# PocketAnalyser_CPLBridge_R01.net
KiCad netlist of a schematic drawn in Altium Designer
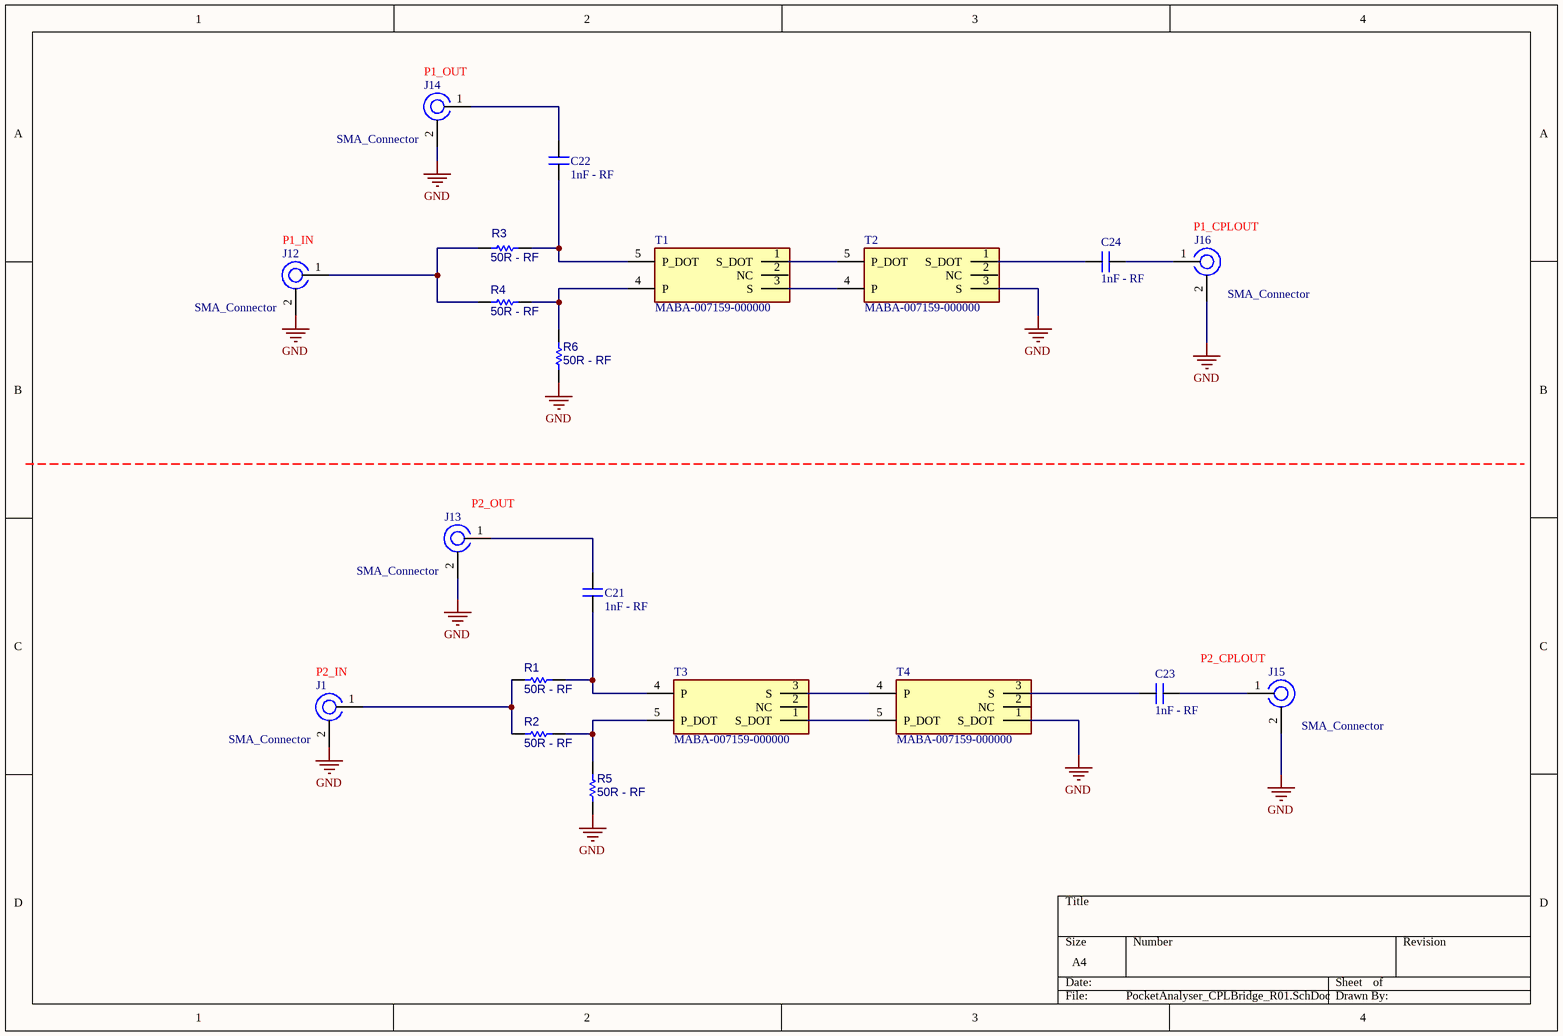
[diagram p0: PocketAnalyser_CPLBridge_R01.SchDoc]

(export (version "E")
  (design (tool "Eeschema 10.0.6"))
  (components
    (comp (ref "C21")
      (value "1nF - RF")
      (footprint "C_0603")
      (libsource (lib "SchLib_PocketAnalyzer") (part "Ceramic Cap"))
    )
    (comp (ref "C22")
      (value "1nF - RF")
      (footprint "C_0603")
      (libsource (lib "SchLib_PocketAnalyzer") (part "Ceramic Cap"))
    )
    (comp (ref "C23")
      (value "1nF - RF")
      (footprint "C_0603")
      (libsource (lib "SchLib_PocketAnalyzer") (part "Ceramic Cap"))
    )
    (comp (ref "C24")
      (value "1nF - RF")
      (footprint "C_0603")
      (libsource (lib "SchLib_PocketAnalyzer") (part "Ceramic Cap"))
    )
    (comp (ref "J1")
      (value "SMA_Connector")
      (footprint "SMA_Connector")
      (description "Connector SMA")
      (libsource (lib "") (part "SMA_Connector_1"))
    )
    (comp (ref "J12")
      (value "SMA_Connector")
      (footprint "SMA_Connector")
      (description "Connector SMA")
      (libsource (lib "") (part "SMA_Connector_1"))
    )
    (comp (ref "J13")
      (value "SMA_Connector")
      (footprint "SMA_Connector")
      (description "Connector SMA")
      (libsource (lib "") (part "SMA_Connector_1"))
    )
    (comp (ref "J14")
      (value "SMA_Connector")
      (footprint "SMA_Connector")
      (description "Connector SMA")
      (libsource (lib "") (part "SMA_Connector_1"))
    )
    (comp (ref "J15")
      (value "SMA_Connector")
      (footprint "SMA_Connector")
      (description "Connector SMA")
      (libsource (lib "SchLib_PocketAnalyzer") (part "SMA_Connector"))
    )
    (comp (ref "J16")
      (value "SMA_Connector")
      (footprint "SMA_Connector")
      (description "Connector SMA")
      (libsource (lib "SchLib_PocketAnalyzer") (part "SMA_Connector"))
    )
    (comp (ref "R1")
      (value "50R - RF")
      (footprint "R_0603")
      (description "Resistor")
      (libsource (lib "SchLib_PocketAnalyzer") (part "Res1"))
    )
    (comp (ref "R2")
      (value "50R - RF")
      (footprint "R_0603")
      (description "Resistor")
      (libsource (lib "SchLib_PocketAnalyzer") (part "Res1"))
    )
    (comp (ref "R3")
      (value "50R - RF")
      (footprint "R_0603")
      (description "Resistor")
      (libsource (lib "SchLib_PocketAnalyzer") (part "Res1"))
    )
    (comp (ref "R4")
      (value "50R - RF")
      (footprint "R_0603")
      (description "Resistor")
      (libsource (lib "SchLib_PocketAnalyzer") (part "Res1"))
    )
    (comp (ref "R5")
      (value "50R - RF")
      (footprint "R_0603")
      (description "Resistor")
      (libsource (lib "SchLib_PocketAnalyzer") (part "Res1"))
    )
    (comp (ref "R6")
      (value "50R - RF")
      (footprint "R_0603")
      (description "Resistor")
      (libsource (lib "SchLib_PocketAnalyzer") (part "Res1"))
    )
    (comp (ref "T1")
      (value "MABA-007159-000000")
      (footprint "MABA-007159-000000_1")
      (description "Transformer")
      (fields (field (name "MOUSER PART NUMBER") "937-MABA007159000000"))
      (libsource (lib "") (part "MABA-007159-000000_1"))
    )
    (comp (ref "T2")
      (value "MABA-007159-000000")
      (footprint "MABA-007159-000000_1")
      (description "Transformer")
      (fields (field (name "MOUSER PART NUMBER") "937-MABA007159000000"))
      (libsource (lib "") (part "MABA-007159-000000_1"))
    )
    (comp (ref "T3")
      (value "MABA-007159-000000")
      (footprint "MABA-007159-000000_1")
      (description "Transformer")
      (fields (field (name "MOUSER PART NUMBER") "937-MABA007159000000"))
      (libsource (lib "SchLib_PocketAnalyzer") (part "MABA-007159-000000"))
    )
    (comp (ref "T4")
      (value "MABA-007159-000000")
      (footprint "MABA-007159-000000_1")
      (description "Transformer")
      (fields (field (name "MOUSER PART NUMBER") "937-MABA007159000000"))
      (libsource (lib "SchLib_PocketAnalyzer") (part "MABA-007159-000000"))
    )
  )
  (nets
    (net (code "1") (name "GND") (class "Default")
      (node (ref "J1") (pin "2") (pinfunction "2_2") (pintype "passive"))
      (node (ref "J12") (pin "2") (pinfunction "2_2") (pintype "passive"))
      (node (ref "J13") (pin "2") (pinfunction "2_2") (pintype "passive"))
      (node (ref "J14") (pin "2") (pinfunction "2_2") (pintype "passive"))
      (node (ref "J15") (pin "2") (pinfunction "2_2") (pintype "passive"))
      (node (ref "J16") (pin "2") (pinfunction "2_2") (pintype "passive"))
      (node (ref "R5") (pin "1") (pinfunction "1_1") (pintype "passive"))
      (node (ref "R6") (pin "1") (pinfunction "1_1") (pintype "passive"))
      (node (ref "T2") (pin "3") (pinfunction "S_3") (pintype "passive"))
      (node (ref "T4") (pin "1") (pinfunction "S_DOT_1") (pintype "passive"))
    )
    (net (code "2") (name "Net-(C21-Pad2)") (class "Default")
      (node (ref "C21") (pin "2") (pintype "passive"))
      (node (ref "J13") (pin "1") (pinfunction "1_1") (pintype "passive"))
    )
    (net (code "3") (name "Net-(C22-Pad2)") (class "Default")
      (node (ref "C22") (pin "2") (pintype "passive"))
      (node (ref "J14") (pin "1") (pinfunction "1_1") (pintype "passive"))
    )
    (net (code "4") (name "Net-(C23-Pad1)") (class "Default")
      (node (ref "C23") (pin "1") (pintype "passive"))
      (node (ref "J15") (pin "1") (pinfunction "1_1") (pintype "passive"))
    )
    (net (code "5") (name "Net-(C24-Pad1)") (class "Default")
      (node (ref "C24") (pin "1") (pintype "passive"))
      (node (ref "J16") (pin "1") (pinfunction "1_1") (pintype "passive"))
    )
    (net (code "6") (name "Net-(J1-Pad1)") (class "Default")
      (node (ref "J1") (pin "1") (pinfunction "1_1") (pintype "passive"))
      (node (ref "R1") (pin "2") (pinfunction "2_2") (pintype "passive"))
      (node (ref "R2") (pin "2") (pinfunction "2_2") (pintype "passive"))
    )
    (net (code "7") (name "Net-(J12-Pad1)") (class "Default")
      (node (ref "J12") (pin "1") (pinfunction "1_1") (pintype "passive"))
      (node (ref "R3") (pin "2") (pinfunction "2_2") (pintype "passive"))
      (node (ref "R4") (pin "2") (pinfunction "2_2") (pintype "passive"))
    )
    (net (code "8") (name "Net-(T1-P)") (class "Default")
      (node (ref "R4") (pin "1") (pinfunction "1_1") (pintype "passive"))
      (node (ref "R6") (pin "2") (pinfunction "2_2") (pintype "passive"))
      (node (ref "T1") (pin "4") (pinfunction "P_4") (pintype "passive"))
    )
    (net (code "9") (name "Net-(T1-P_DOT)") (class "Default")
      (node (ref "C22") (pin "1") (pintype "passive"))
      (node (ref "R3") (pin "1") (pinfunction "1_1") (pintype "passive"))
      (node (ref "T1") (pin "5") (pinfunction "P_DOT_5") (pintype "passive"))
    )
    (net (code "10") (name "Net-(T1-S)") (class "Default")
      (node (ref "T1") (pin "3") (pinfunction "S_3") (pintype "passive"))
      (node (ref "T2") (pin "4") (pinfunction "P_4") (pintype "passive"))
    )
    (net (code "11") (name "Net-(T1-S_DOT)") (class "Default")
      (node (ref "T1") (pin "1") (pinfunction "S_DOT_1") (pintype "passive"))
      (node (ref "T2") (pin "5") (pinfunction "P_DOT_5") (pintype "passive"))
    )
    (net (code "12") (name "Net-(T2-S_DOT)") (class "Default")
      (node (ref "C24") (pin "2") (pintype "passive"))
      (node (ref "T2") (pin "1") (pinfunction "S_DOT_1") (pintype "passive"))
    )
    (net (code "13") (name "Net-(T3-P)") (class "Default")
      (node (ref "C21") (pin "1") (pintype "passive"))
      (node (ref "R1") (pin "1") (pinfunction "1_1") (pintype "passive"))
      (node (ref "T3") (pin "4") (pinfunction "P_4") (pintype "passive"))
    )
    (net (code "14") (name "Net-(T3-P_DOT)") (class "Default")
      (node (ref "R2") (pin "1") (pinfunction "1_1") (pintype "passive"))
      (node (ref "R5") (pin "2") (pinfunction "2_2") (pintype "passive"))
      (node (ref "T3") (pin "5") (pinfunction "P_DOT_5") (pintype "passive"))
    )
    (net (code "15") (name "Net-(T3-S)") (class "Default")
      (node (ref "T3") (pin "3") (pinfunction "S_3") (pintype "passive"))
      (node (ref "T4") (pin "4") (pinfunction "P_4") (pintype "passive"))
    )
    (net (code "16") (name "Net-(T3-S_DOT)") (class "Default")
      (node (ref "T3") (pin "1") (pinfunction "S_DOT_1") (pintype "passive"))
      (node (ref "T4") (pin "5") (pinfunction "P_DOT_5") (pintype "passive"))
    )
    (net (code "17") (name "Net-(T4-S)") (class "Default")
      (node (ref "C23") (pin "2") (pintype "passive"))
      (node (ref "T4") (pin "3") (pinfunction "S_3") (pintype "passive"))
    )
    (net (code "18") (name "unconnected-(T1-NC-Pad2)") (class "Default")
      (node (ref "T1") (pin "2") (pinfunction "NC_2") (pintype "passive"))
    )
    (net (code "19") (name "unconnected-(T2-NC-Pad2)") (class "Default")
      (node (ref "T2") (pin "2") (pinfunction "NC_2") (pintype "passive"))
    )
    (net (code "20") (name "unconnected-(T3-NC-Pad2)") (class "Default")
      (node (ref "T3") (pin "2") (pinfunction "NC_2") (pintype "passive"))
    )
    (net (code "21") (name "unconnected-(T4-NC-Pad2)") (class "Default")
      (node (ref "T4") (pin "2") (pinfunction "NC_2") (pintype "passive"))
    )
  )
)
